# pico_v1.net
KiCad netlist of a schematic drawn in Altium Designer
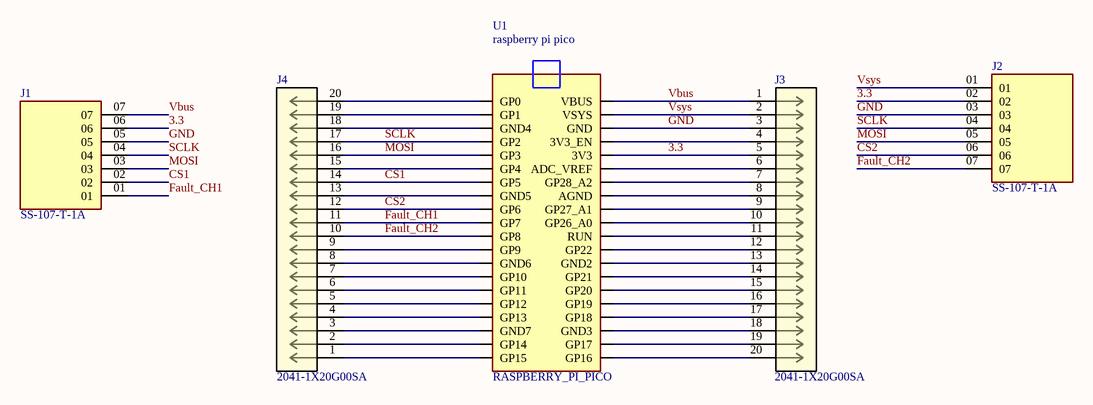
[diagram p0: pico_v1.SchDoc]

(export (version "E")
  (design (tool "Eeschema 10.0.6"))
  (components
    (comp (ref "J1")
      (value "SS-107-T-1A")
      (footprint "SAMTEC_SS-107-T-1A")
      (libsource (lib "") (part "SS-107-T-1A_1"))
    )
    (comp (ref "J2")
      (value "SS-107-T-1A")
      (footprint "SAMTEC_SS-107-T-1A")
      (libsource (lib "SS-107-T-1A") (part "SS-107-T-1A"))
    )
    (comp (ref "J3")
      (value "2041-1X20G00SA")
      (footprint "CONN_2041-1X20xxxSx_OUP")
      (description "Description")
      (fields (field (name "COPYRIGHT") "Copyright (C) 2025 Ultra Librarian. All rights reserved."))
      (libsource (lib "2041-1X20G00SA") (part "2041-1X20G00SA"))
    )
    (comp (ref "J4")
      (value "2041-1X20G00SA")
      (footprint "CONN_2041-1X20xxxSx_OUP")
      (description "Description")
      (fields (field (name "COPYRIGHT") "Copyright (C) 2025 Ultra Librarian. All rights reserved."))
      (libsource (lib "2041-1X20G00SA") (part "2041-1X20G00SA"))
    )
    (comp (ref "U1")
      (value "RASPBERRY_PI_PICO")
      (footprint "RASPBERRY_PI_PICO")
      (fields (field (name "MF") "Raspberry Pi") (field (name "MP") "RASPBERRY PI PICO"))
      (libsource (lib "RASPBERRY_PI_PICO") (part "RASPBERRY_PI_PICO"))
    )
  )
  (nets
    (net (code "1") (name "/3.3") (class "Default")
      (node (ref "J1") (pin "06") (pinfunction "06_06") (pintype "passive"))
      (node (ref "J2") (pin "02") (pinfunction "02_02") (pintype "passive"))
      (node (ref "J3") (pin "5") (pinfunction "5_5") (pintype "passive"))
      (node (ref "U1") (pin "3V3") (pinfunction "3V3_3V3") (pintype "bidirectional"))
    )
    (net (code "2") (name "/CS1") (class "Default")
      (node (ref "J1") (pin "02") (pinfunction "02_02") (pintype "passive"))
      (node (ref "J4") (pin "14") (pinfunction "14_14") (pintype "passive"))
      (node (ref "U1") (pin "GP5") (pinfunction "GP5_GP5") (pintype "bidirectional"))
    )
    (net (code "3") (name "/CS2") (class "Default")
      (node (ref "J2") (pin "06") (pinfunction "06_06") (pintype "passive"))
      (node (ref "J4") (pin "12") (pinfunction "12_12") (pintype "passive"))
      (node (ref "U1") (pin "GP6") (pinfunction "GP6_GP6") (pintype "bidirectional"))
    )
    (net (code "4") (name "/Fault_CH1") (class "Default")
      (node (ref "J1") (pin "01") (pinfunction "01_01") (pintype "passive"))
      (node (ref "J4") (pin "11") (pinfunction "11_11") (pintype "passive"))
      (node (ref "U1") (pin "GP7") (pinfunction "GP7_GP7") (pintype "bidirectional"))
    )
    (net (code "5") (name "/Fault_CH2") (class "Default")
      (node (ref "J2") (pin "07") (pinfunction "07_07") (pintype "passive"))
      (node (ref "J4") (pin "10") (pinfunction "10_10") (pintype "passive"))
      (node (ref "U1") (pin "GP8") (pinfunction "GP8_GP8") (pintype "bidirectional"))
    )
    (net (code "6") (name "/GND") (class "Default")
      (node (ref "J1") (pin "05") (pinfunction "05_05") (pintype "passive"))
      (node (ref "J2") (pin "03") (pinfunction "03_03") (pintype "passive"))
      (node (ref "J3") (pin "3") (pinfunction "3_3") (pintype "passive"))
      (node (ref "U1") (pin "GND") (pinfunction "GND_GND") (pintype "bidirectional"))
    )
    (net (code "7") (name "/MOSI") (class "Default")
      (node (ref "J1") (pin "03") (pinfunction "03_03") (pintype "passive"))
      (node (ref "J2") (pin "05") (pinfunction "05_05") (pintype "passive"))
      (node (ref "J4") (pin "16") (pinfunction "16_16") (pintype "passive"))
      (node (ref "U1") (pin "GP3") (pinfunction "GP3_GP3") (pintype "bidirectional"))
    )
    (net (code "8") (name "/SCLK") (class "Default")
      (node (ref "J1") (pin "04") (pinfunction "04_04") (pintype "passive"))
      (node (ref "J2") (pin "04") (pinfunction "04_04") (pintype "passive"))
      (node (ref "J4") (pin "17") (pinfunction "17_17") (pintype "passive"))
      (node (ref "U1") (pin "GP2") (pinfunction "GP2_GP2") (pintype "bidirectional"))
    )
    (net (code "9") (name "/Vbus") (class "Default")
      (node (ref "J1") (pin "07") (pinfunction "07_07") (pintype "passive"))
      (node (ref "J3") (pin "1") (pinfunction "1_1") (pintype "passive"))
      (node (ref "U1") (pin "VBUS") (pinfunction "VBUS_VBUS") (pintype "bidirectional"))
    )
    (net (code "10") (name "/Vsys") (class "Default")
      (node (ref "J2") (pin "01") (pinfunction "01_01") (pintype "passive"))
      (node (ref "J3") (pin "2") (pinfunction "2_2") (pintype "passive"))
      (node (ref "U1") (pin "VSYS") (pinfunction "VSYS_VSYS") (pintype "bidirectional"))
    )
    (net (code "11") (name "Net-(J3-Pad4)") (class "Default")
      (node (ref "J3") (pin "4") (pinfunction "4_4") (pintype "passive"))
      (node (ref "U1") (pin "3V3_EN") (pinfunction "3V3_EN_3V3_EN") (pintype "bidirectional"))
    )
    (net (code "12") (name "Net-(J3-Pad6)") (class "Default")
      (node (ref "J3") (pin "6") (pinfunction "6_6") (pintype "passive"))
      (node (ref "U1") (pin "ADC_VREF") (pinfunction "ADC_VREF_ADC_VREF") (pintype "bidirectional"))
    )
    (net (code "13") (name "Net-(J3-Pad7)") (class "Default")
      (node (ref "J3") (pin "7") (pinfunction "7_7") (pintype "passive"))
      (node (ref "U1") (pin "GP28_A2") (pinfunction "GP28_A2_GP28_A2") (pintype "bidirectional"))
    )
    (net (code "14") (name "Net-(J3-Pad8)") (class "Default")
      (node (ref "J3") (pin "8") (pinfunction "8_8") (pintype "passive"))
      (node (ref "U1") (pin "AGND") (pinfunction "AGND_AGND") (pintype "bidirectional"))
    )
    (net (code "15") (name "Net-(J3-Pad9)") (class "Default")
      (node (ref "J3") (pin "9") (pinfunction "9_9") (pintype "passive"))
      (node (ref "U1") (pin "GP27_A1") (pinfunction "GP27_A1_GP27_A1") (pintype "bidirectional"))
    )
    (net (code "16") (name "Net-(J3-Pad10)") (class "Default")
      (node (ref "J3") (pin "10") (pinfunction "10_10") (pintype "passive"))
      (node (ref "U1") (pin "GP26_A0") (pinfunction "GP26_A0_GP26_A0") (pintype "bidirectional"))
    )
    (net (code "17") (name "Net-(J3-Pad11)") (class "Default")
      (node (ref "J3") (pin "11") (pinfunction "11_11") (pintype "passive"))
      (node (ref "U1") (pin "RUN") (pinfunction "RUN_RUN") (pintype "bidirectional"))
    )
    (net (code "18") (name "Net-(J3-Pad12)") (class "Default")
      (node (ref "J3") (pin "12") (pinfunction "12_12") (pintype "passive"))
      (node (ref "U1") (pin "GP22") (pinfunction "GP22_GP22") (pintype "bidirectional"))
    )
    (net (code "19") (name "Net-(J3-Pad13)") (class "Default")
      (node (ref "J3") (pin "13") (pinfunction "13_13") (pintype "passive"))
      (node (ref "U1") (pin "GND2") (pinfunction "GND2_GND2") (pintype "bidirectional"))
    )
    (net (code "20") (name "Net-(J3-Pad14)") (class "Default")
      (node (ref "J3") (pin "14") (pinfunction "14_14") (pintype "passive"))
      (node (ref "U1") (pin "GP21") (pinfunction "GP21_GP21") (pintype "bidirectional"))
    )
    (net (code "21") (name "Net-(J3-Pad15)") (class "Default")
      (node (ref "J3") (pin "15") (pinfunction "15_15") (pintype "passive"))
      (node (ref "U1") (pin "GP20") (pinfunction "GP20_GP20") (pintype "bidirectional"))
    )
    (net (code "22") (name "Net-(J3-Pad16)") (class "Default")
      (node (ref "J3") (pin "16") (pinfunction "16_16") (pintype "passive"))
      (node (ref "U1") (pin "GP19") (pinfunction "GP19_GP19") (pintype "bidirectional"))
    )
    (net (code "23") (name "Net-(J3-Pad17)") (class "Default")
      (node (ref "J3") (pin "17") (pinfunction "17_17") (pintype "passive"))
      (node (ref "U1") (pin "GP18") (pinfunction "GP18_GP18") (pintype "bidirectional"))
    )
    (net (code "24") (name "Net-(J3-Pad18)") (class "Default")
      (node (ref "J3") (pin "18") (pinfunction "18_18") (pintype "passive"))
      (node (ref "U1") (pin "GND3") (pinfunction "GND3_GND3") (pintype "bidirectional"))
    )
    (net (code "25") (name "Net-(J3-Pad19)") (class "Default")
      (node (ref "J3") (pin "19") (pinfunction "19_19") (pintype "passive"))
      (node (ref "U1") (pin "GP17") (pinfunction "GP17_GP17") (pintype "bidirectional"))
    )
    (net (code "26") (name "Net-(J3-Pad20)") (class "Default")
      (node (ref "J3") (pin "20") (pinfunction "20_20") (pintype "passive"))
      (node (ref "U1") (pin "GP16") (pinfunction "GP16_GP16") (pintype "bidirectional"))
    )
    (net (code "27") (name "Net-(J4-Pad1)") (class "Default")
      (node (ref "J4") (pin "1") (pinfunction "1_1") (pintype "passive"))
      (node (ref "U1") (pin "GP15") (pinfunction "GP15_GP15") (pintype "bidirectional"))
    )
    (net (code "28") (name "Net-(J4-Pad2)") (class "Default")
      (node (ref "J4") (pin "2") (pinfunction "2_2") (pintype "passive"))
      (node (ref "U1") (pin "GP14") (pinfunction "GP14_GP14") (pintype "bidirectional"))
    )
    (net (code "29") (name "Net-(J4-Pad3)") (class "Default")
      (node (ref "J4") (pin "3") (pinfunction "3_3") (pintype "passive"))
      (node (ref "U1") (pin "GND7") (pinfunction "GND7_GND7") (pintype "bidirectional"))
    )
    (net (code "30") (name "Net-(J4-Pad4)") (class "Default")
      (node (ref "J4") (pin "4") (pinfunction "4_4") (pintype "passive"))
      (node (ref "U1") (pin "GP13") (pinfunction "GP13_GP13") (pintype "bidirectional"))
    )
    (net (code "31") (name "Net-(J4-Pad5)") (class "Default")
      (node (ref "J4") (pin "5") (pinfunction "5_5") (pintype "passive"))
      (node (ref "U1") (pin "GP12") (pinfunction "GP12_GP12") (pintype "bidirectional"))
    )
    (net (code "32") (name "Net-(J4-Pad6)") (class "Default")
      (node (ref "J4") (pin "6") (pinfunction "6_6") (pintype "passive"))
      (node (ref "U1") (pin "GP11") (pinfunction "GP11_GP11") (pintype "bidirectional"))
    )
    (net (code "33") (name "Net-(J4-Pad7)") (class "Default")
      (node (ref "J4") (pin "7") (pinfunction "7_7") (pintype "passive"))
      (node (ref "U1") (pin "GP10") (pinfunction "GP10_GP10") (pintype "bidirectional"))
    )
    (net (code "34") (name "Net-(J4-Pad8)") (class "Default")
      (node (ref "J4") (pin "8") (pinfunction "8_8") (pintype "passive"))
      (node (ref "U1") (pin "GND6") (pinfunction "GND6_GND6") (pintype "bidirectional"))
    )
    (net (code "35") (name "Net-(J4-Pad9)") (class "Default")
      (node (ref "J4") (pin "9") (pinfunction "9_9") (pintype "passive"))
      (node (ref "U1") (pin "GP9") (pinfunction "GP9_GP9") (pintype "bidirectional"))
    )
    (net (code "36") (name "Net-(J4-Pad13)") (class "Default")
      (node (ref "J4") (pin "13") (pinfunction "13_13") (pintype "passive"))
      (node (ref "U1") (pin "GND5") (pinfunction "GND5_GND5") (pintype "bidirectional"))
    )
    (net (code "37") (name "Net-(J4-Pad15)") (class "Default")
      (node (ref "J4") (pin "15") (pinfunction "15_15") (pintype "passive"))
      (node (ref "U1") (pin "GP4") (pinfunction "GP4_GP4") (pintype "bidirectional"))
    )
    (net (code "38") (name "Net-(J4-Pad18)") (class "Default")
      (node (ref "J4") (pin "18") (pinfunction "18_18") (pintype "passive"))
      (node (ref "U1") (pin "GND4") (pinfunction "GND4_GND4") (pintype "bidirectional"))
    )
    (net (code "39") (name "Net-(J4-Pad19)") (class "Default")
      (node (ref "J4") (pin "19") (pinfunction "19_19") (pintype "passive"))
      (node (ref "U1") (pin "GP1") (pinfunction "GP1_GP1") (pintype "bidirectional"))
    )
    (net (code "40") (name "Net-(J4-Pad20)") (class "Default")
      (node (ref "J4") (pin "20") (pinfunction "20_20") (pintype "passive"))
      (node (ref "U1") (pin "GP0") (pinfunction "GP0_GP0") (pintype "bidirectional"))
    )
  )
)
